# Extension.net
KiCad netlist of a schematic drawn in EAGLE
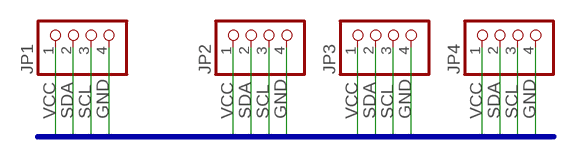
[diagram p0: schematic, sheet 1]
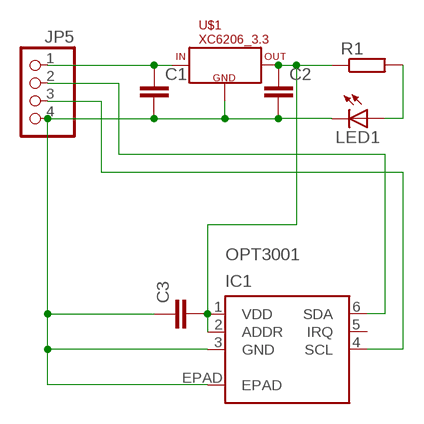
[diagram p1: schematic, sheet 2]

(export (version "E")
  (design (tool "Eeschema 10.0.6"))
  (components
    (comp (ref "JP1")
      (value "PINHD-1X4")
      (footprint "eagle-import:1X04")
      (libsource (lib "eagle-import") (part "PINHD-1X4"))
    )
    (comp (ref "JP2")
      (value "PINHD-1X4")
      (footprint "eagle-import:1X04")
      (libsource (lib "eagle-import") (part "PINHD-1X4"))
    )
    (comp (ref "JP3")
      (value "PINHD-1X4")
      (footprint "eagle-import:1X04")
      (libsource (lib "eagle-import") (part "PINHD-1X4"))
    )
    (comp (ref "JP4")
      (value "PINHD-1X4")
      (footprint "eagle-import:1X04")
      (libsource (lib "eagle-import") (part "PINHD-1X4"))
    )
    (comp (ref "C1")
      (value "C-EUC0805")
      (footprint "eagle-import:C0805")
      (libsource (lib "eagle-import") (part "C-EUC0805"))
    )
    (comp (ref "C2")
      (value "C-EUC0805")
      (footprint "eagle-import:C0805")
      (libsource (lib "eagle-import") (part "C-EUC0805"))
    )
    (comp (ref "C3")
      (value "C-EUC0805")
      (footprint "eagle-import:C0805")
      (libsource (lib "eagle-import") (part "C-EUC0805"))
    )
    (comp (ref "IC1")
      (value "OPT3001")
      (footprint "eagle-import:USON6")
      (libsource (lib "eagle-import") (part "OPT3001"))
    )
    (comp (ref "JP5")
      (value "PINHD-1X4")
      (footprint "eagle-import:1X04")
      (libsource (lib "eagle-import") (part "PINHD-1X4"))
    )
    (comp (ref "LED1")
      (value "LEDCHIPLED_0805")
      (footprint "eagle-import:CHIPLED_0805")
      (libsource (lib "eagle-import") (part "LEDCHIPLED_0805"))
    )
    (comp (ref "R1")
      (value "R-EU_R0805")
      (footprint "eagle-import:R0805")
      (libsource (lib "eagle-import") (part "R-EU_R0805"))
    )
    (comp (ref "U$1")
      (value "XC6206_3.3")
      (footprint "eagle-import:SOT23")
      (libsource (lib "eagle-import") (part "XC6206_3.3"))
    )
  )
  (nets
    (net (code "1") (name "GND") (class "Default")
      (node (ref "JP1") (pin "4") (pinfunction "4_4") (pintype "passive"))
      (node (ref "JP2") (pin "4") (pinfunction "4_4") (pintype "passive"))
      (node (ref "JP3") (pin "4") (pinfunction "4_4") (pintype "passive"))
      (node (ref "JP4") (pin "4") (pinfunction "4_4") (pintype "passive"))
    )
    (net (code "2") (name "Net-(IC1-ADDR)") (class "Default")
      (node (ref "C2") (pin "1") (pinfunction "1_1") (pintype "passive"))
      (node (ref "C3") (pin "2") (pinfunction "2_2") (pintype "passive"))
      (node (ref "IC1") (pin "1") (pinfunction "VDD_1") (pintype "power_in"))
      (node (ref "IC1") (pin "2") (pinfunction "ADDR_2") (pintype "bidirectional"))
      (node (ref "R1") (pin "1") (pinfunction "1_1") (pintype "passive"))
      (node (ref "U$1") (pin "2") (pinfunction "OUT_2") (pintype "power_in"))
    )
    (net (code "3") (name "Net-(IC1-GND)") (class "Default")
      (node (ref "C1") (pin "2") (pinfunction "2_2") (pintype "passive"))
      (node (ref "C2") (pin "2") (pinfunction "2_2") (pintype "passive"))
      (node (ref "C3") (pin "1") (pinfunction "1_1") (pintype "passive"))
      (node (ref "IC1") (pin "3") (pinfunction "GND_3") (pintype "power_in"))
      (node (ref "IC1") (pin "EPAD") (pinfunction "EPAD_EPAD") (pintype "bidirectional"))
      (node (ref "JP5") (pin "4") (pinfunction "4_4") (pintype "passive"))
      (node (ref "LED1") (pin "C") (pinfunction "C_C") (pintype "passive"))
      (node (ref "U$1") (pin "1") (pinfunction "GND_1") (pintype "power_in"))
    )
    (net (code "4") (name "Net-(IC1-SCL)") (class "Default")
      (node (ref "IC1") (pin "4") (pinfunction "SCL_4") (pintype "bidirectional"))
      (node (ref "JP5") (pin "3") (pinfunction "3_3") (pintype "passive"))
    )
    (net (code "5") (name "Net-(IC1-SDA)") (class "Default")
      (node (ref "IC1") (pin "6") (pinfunction "SDA_6") (pintype "bidirectional"))
      (node (ref "JP5") (pin "2") (pinfunction "2_2") (pintype "passive"))
    )
    (net (code "6") (name "Net-(LED1-PadA)") (class "Default")
      (node (ref "LED1") (pin "A") (pinfunction "A_A") (pintype "passive"))
      (node (ref "R1") (pin "2") (pinfunction "2_2") (pintype "passive"))
    )
    (net (code "7") (name "Net-(U$1-IN)") (class "Default")
      (node (ref "C1") (pin "1") (pinfunction "1_1") (pintype "passive"))
      (node (ref "JP5") (pin "1") (pinfunction "1_1") (pintype "passive"))
      (node (ref "U$1") (pin "3") (pinfunction "IN_3") (pintype "power_in"))
    )
    (net (code "8") (name "SCL") (class "Default")
      (node (ref "JP1") (pin "3") (pinfunction "3_3") (pintype "passive"))
      (node (ref "JP2") (pin "3") (pinfunction "3_3") (pintype "passive"))
      (node (ref "JP3") (pin "3") (pinfunction "3_3") (pintype "passive"))
      (node (ref "JP4") (pin "3") (pinfunction "3_3") (pintype "passive"))
    )
    (net (code "9") (name "SDA") (class "Default")
      (node (ref "JP1") (pin "2") (pinfunction "2_2") (pintype "passive"))
      (node (ref "JP2") (pin "2") (pinfunction "2_2") (pintype "passive"))
      (node (ref "JP3") (pin "2") (pinfunction "2_2") (pintype "passive"))
      (node (ref "JP4") (pin "2") (pinfunction "2_2") (pintype "passive"))
    )
    (net (code "10") (name "VCC") (class "Default")
      (node (ref "JP1") (pin "1") (pinfunction "1_1") (pintype "passive"))
      (node (ref "JP2") (pin "1") (pinfunction "1_1") (pintype "passive"))
      (node (ref "JP3") (pin "1") (pinfunction "1_1") (pintype "passive"))
      (node (ref "JP4") (pin "1") (pinfunction "1_1") (pintype "passive"))
    )
    (net (code "11") (name "unconnected-(IC1-IRQ-Pad5)") (class "Default")
      (node (ref "IC1") (pin "5") (pinfunction "IRQ_5") (pintype "bidirectional"))
    )
  )
)
